# MCU_et_Communication.net
KiCad netlist of a schematic drawn in Altium Designer
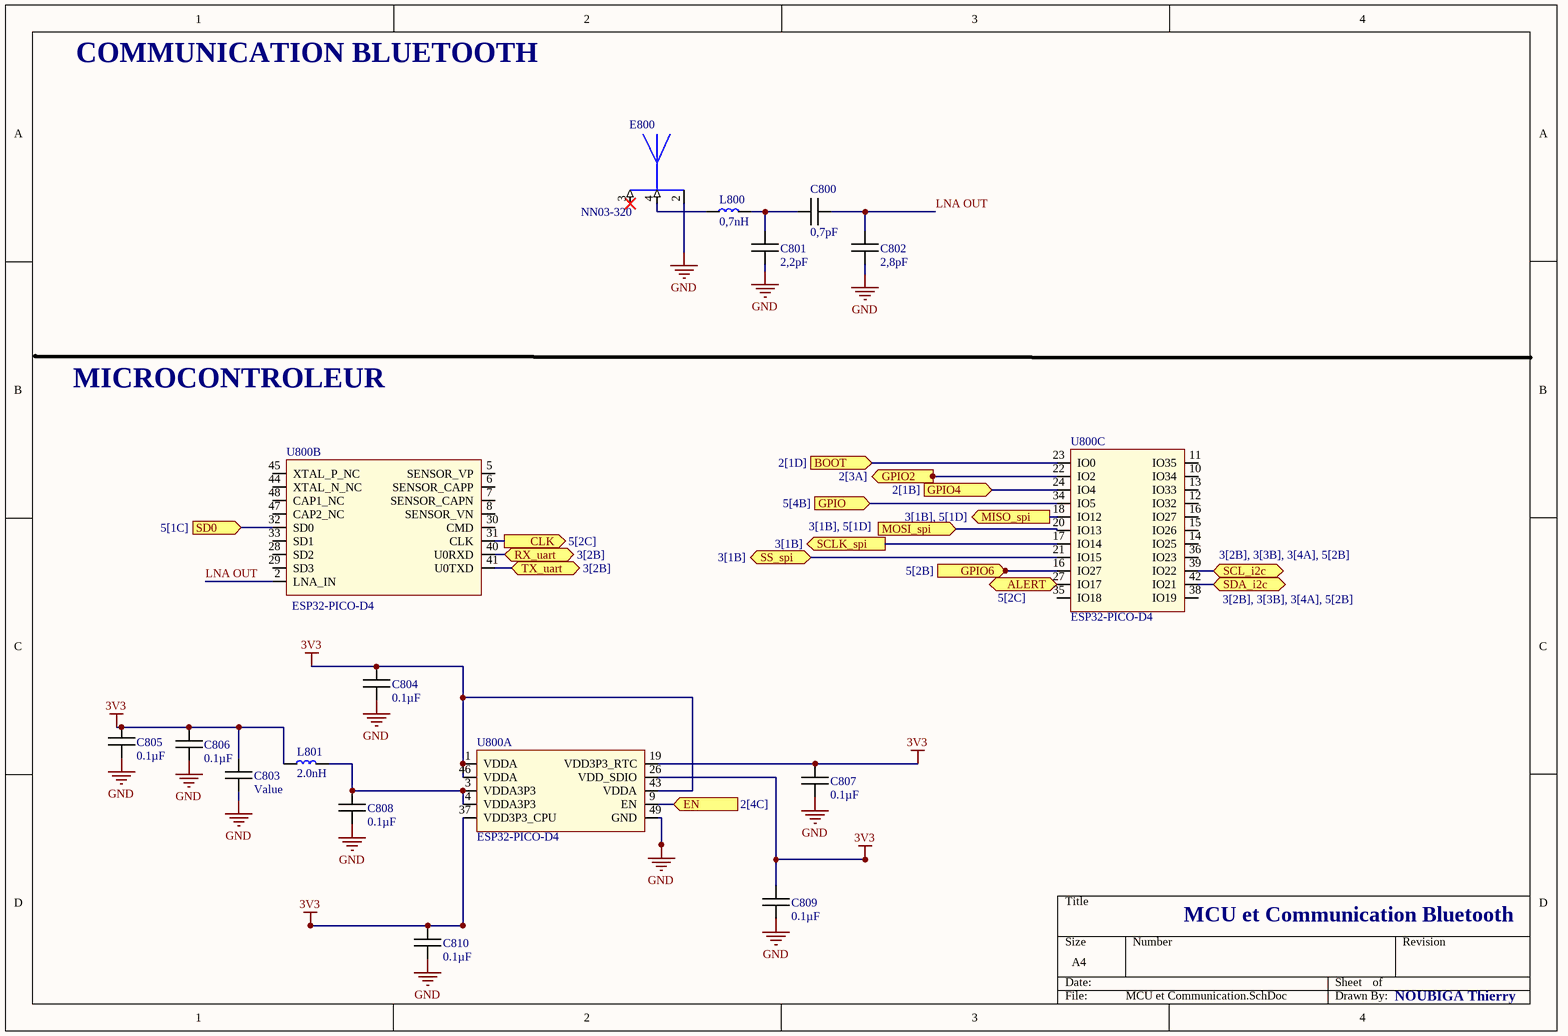
[diagram p0: MCU et Communication.SchDoc]

(export (version "E")
  (design (tool "Eeschema 10.0.6"))
  (components
    (comp (ref "C800")
      (value "0,7pF")
      (footprint "CAPC1005X06N")
      (libsource (lib "SCHLibrary") (part "Capacitor"))
    )
    (comp (ref "C801")
      (value "2,2pF")
      (footprint "CAPC1005X06N")
      (libsource (lib "SCHLibrary") (part "Capacitor"))
    )
    (comp (ref "C802")
      (value "2,8pF")
      (footprint "CAPC1005X06N")
      (libsource (lib "SCHLibrary") (part "Capacitor"))
    )
    (comp (ref "C803")
      (value "Value")
      (footprint "CAPC1005X06N")
      (libsource (lib "SCHLibrary") (part "Capacitor"))
    )
    (comp (ref "C804")
      (value "0.1µF")
      (footprint "CAPC1005X06N")
      (libsource (lib "SCHLibrary") (part "Capacitor"))
    )
    (comp (ref "C805")
      (value "0.1µF")
      (footprint "CAPC1005X06N")
      (libsource (lib "SCHLibrary") (part "Capacitor"))
    )
    (comp (ref "C806")
      (value "0.1µF")
      (footprint "CAPC1005X06N")
      (libsource (lib "SCHLibrary") (part "Capacitor"))
    )
    (comp (ref "C807")
      (value "0.1µF")
      (footprint "CAPC1005X06N")
      (libsource (lib "SCHLibrary") (part "Capacitor"))
    )
    (comp (ref "C808")
      (value "0.1µF")
      (footprint "CAPC1005X06N")
      (libsource (lib "SCHLibrary") (part "Capacitor"))
    )
    (comp (ref "C809")
      (value "0.1µF")
      (footprint "CAPC1005X06N")
      (libsource (lib "SCHLibrary") (part "Capacitor"))
    )
    (comp (ref "C810")
      (value "0.1µF")
      (footprint "CAPC1005X06N")
      (libsource (lib "SCHLibrary") (part "Capacitor"))
    )
    (comp (ref "E800")
      (value "NN03-320")
      (footprint "XCVR_NN03-320")
      (fields (field (name "MOUSER PART NUMBER") "128-NN03-320"))
      (libsource (lib "SCHLibrary") (part "NN03-320"))
    )
    (comp (ref "L800")
      (value "0,7nH")
      (footprint "LQPC1005X06N")
      (libsource (lib "SCHLibrary") (part "Bobine"))
    )
    (comp (ref "L801")
      (value "2.0nH")
      (footprint "LQPC1005X06N")
      (libsource (lib "SCHLibrary") (part "Bobine"))
    )
    (comp (ref "U800")
      (value "ESP32-PICO-D4")
      (footprint "PQFN50P700X700X104_HS-49N")
      (libsource (lib "") (part "ESP32_2"))
    )
  )
  (nets
    (net (code "1") (name "/ALERT") (class "Default")
      (node (ref "U800") (pin "27") (pinfunction "IO17_27") (pintype "passive"))
    )
    (net (code "2") (name "/BOOT") (class "Default")
      (node (ref "U800") (pin "23") (pinfunction "IO0_23") (pintype "passive"))
    )
    (net (code "3") (name "/CLK") (class "Default")
      (node (ref "U800") (pin "31") (pinfunction "CLK_31") (pintype "passive"))
    )
    (net (code "4") (name "/EN") (class "Default")
      (node (ref "U800") (pin "9") (pinfunction "EN_9") (pintype "passive"))
    )
    (net (code "5") (name "/GPIO") (class "Default")
      (node (ref "U800") (pin "34") (pinfunction "IO5_34") (pintype "passive"))
    )
    (net (code "6") (name "/GPIO2") (class "Default")
      (node (ref "U800") (pin "22") (pinfunction "IO2_22") (pintype "passive"))
    )
    (net (code "7") (name "/GPIO4") (class "Default")
      (node (ref "U800") (pin "24") (pinfunction "IO4_24") (pintype "passive"))
    )
    (net (code "8") (name "/GPIO6") (class "Default")
      (node (ref "U800") (pin "16") (pinfunction "IO27_16") (pintype "passive"))
    )
    (net (code "9") (name "/LNA OUT") (class "Default")
      (node (ref "C800") (pin "2") (pinfunction "2_2") (pintype "passive"))
      (node (ref "C802") (pin "1") (pinfunction "1_1") (pintype "passive"))
      (node (ref "U800") (pin "2") (pinfunction "LNA_IN_2") (pintype "passive"))
    )
    (net (code "10") (name "/MISO_spi") (class "Default")
      (node (ref "U800") (pin "18") (pinfunction "IO12_18") (pintype "passive"))
    )
    (net (code "11") (name "/MOSI_spi") (class "Default")
      (node (ref "U800") (pin "20") (pinfunction "IO13_20") (pintype "passive"))
    )
    (net (code "12") (name "/RX_uart") (class "Default")
      (node (ref "U800") (pin "40") (pinfunction "U0RXD_40") (pintype "passive"))
    )
    (net (code "13") (name "/SCLK_spi") (class "Default")
      (node (ref "U800") (pin "17") (pinfunction "IO14_17") (pintype "passive"))
    )
    (net (code "14") (name "/SCL_i2c") (class "Default")
      (node (ref "U800") (pin "39") (pinfunction "IO22_39") (pintype "passive"))
    )
    (net (code "15") (name "/SD0") (class "Default")
      (node (ref "U800") (pin "32") (pinfunction "SD0_32") (pintype "passive"))
    )
    (net (code "16") (name "/SDA_i2c") (class "Default")
      (node (ref "U800") (pin "42") (pinfunction "IO21_42") (pintype "passive"))
    )
    (net (code "17") (name "/SS_spi") (class "Default")
      (node (ref "U800") (pin "21") (pinfunction "IO15_21") (pintype "passive"))
    )
    (net (code "18") (name "/TX_uart") (class "Default")
      (node (ref "U800") (pin "41") (pinfunction "U0TXD_41") (pintype "passive"))
    )
    (net (code "19") (name "3V3") (class "Default")
      (node (ref "C803") (pin "1") (pinfunction "1_1") (pintype "passive"))
      (node (ref "C804") (pin "2") (pinfunction "2_2") (pintype "passive"))
      (node (ref "C805") (pin "2") (pinfunction "2_2") (pintype "passive"))
      (node (ref "C806") (pin "2") (pinfunction "2_2") (pintype "passive"))
      (node (ref "C807") (pin "1") (pinfunction "1_1") (pintype "passive"))
      (node (ref "C809") (pin "2") (pinfunction "2_2") (pintype "passive"))
      (node (ref "C810") (pin "1") (pinfunction "1_1") (pintype "passive"))
      (node (ref "L801") (pin "1") (pinfunction "1_1") (pintype "passive"))
      (node (ref "U800") (pin "1") (pinfunction "VDDA_1") (pintype "passive"))
      (node (ref "U800") (pin "19") (pinfunction "VDD3P3_RTC_19") (pintype "passive"))
      (node (ref "U800") (pin "26") (pinfunction "VDD_SDIO_26") (pintype "passive"))
      (node (ref "U800") (pin "37") (pinfunction "VDD3P3_CPU_37") (pintype "passive"))
      (node (ref "U800") (pin "43") (pinfunction "VDDA_43") (pintype "passive"))
      (node (ref "U800") (pin "46") (pinfunction "VDDA_46") (pintype "passive"))
    )
    (net (code "20") (name "GND") (class "Default")
      (node (ref "C801") (pin "2") (pinfunction "2_2") (pintype "passive"))
      (node (ref "C802") (pin "2") (pinfunction "2_2") (pintype "passive"))
      (node (ref "C803") (pin "2") (pinfunction "2_2") (pintype "passive"))
      (node (ref "C804") (pin "1") (pinfunction "1_1") (pintype "passive"))
      (node (ref "C805") (pin "1") (pinfunction "1_1") (pintype "passive"))
      (node (ref "C806") (pin "1") (pinfunction "1_1") (pintype "passive"))
      (node (ref "C807") (pin "2") (pinfunction "2_2") (pintype "passive"))
      (node (ref "C808") (pin "1") (pinfunction "1_1") (pintype "passive"))
      (node (ref "C809") (pin "1") (pinfunction "1_1") (pintype "passive"))
      (node (ref "C810") (pin "2") (pinfunction "2_2") (pintype "passive"))
      (node (ref "E800") (pin "2") (pinfunction "GROUND_2") (pintype "power_in"))
      (node (ref "U800") (pin "49") (pinfunction "GND_49") (pintype "passive"))
    )
    (net (code "21") (name "Net-(C800-Pad1)") (class "Default")
      (node (ref "C800") (pin "1") (pinfunction "1_1") (pintype "passive"))
      (node (ref "C801") (pin "1") (pinfunction "1_1") (pintype "passive"))
      (node (ref "L800") (pin "2") (pinfunction "2_2") (pintype "passive"))
    )
    (net (code "22") (name "Net-(C808-Pad2)") (class "Default")
      (node (ref "C808") (pin "2") (pinfunction "2_2") (pintype "passive"))
      (node (ref "L801") (pin "2") (pinfunction "2_2") (pintype "passive"))
      (node (ref "U800") (pin "3") (pinfunction "VDDA3P3_3") (pintype "passive"))
      (node (ref "U800") (pin "4") (pinfunction "VDDA3P3_4") (pintype "passive"))
    )
    (net (code "23") (name "Net-(E800-FEED_GNSS)") (class "Default")
      (node (ref "E800") (pin "4") (pinfunction "FEED_GNSS_4") (pintype "input"))
      (node (ref "L800") (pin "1") (pinfunction "1_1") (pintype "passive"))
    )
    (net (code "24") (name "unconnected-(E800-FEED_BLUETOOTH-Pad3)") (class "Default")
      (node (ref "E800") (pin "3") (pinfunction "FEED_BLUETOOTH_3") (pintype "input+no_connect"))
    )
    (net (code "25") (name "unconnected-(U800B-CAP1_NC-Pad48)") (class "Default")
      (node (ref "U800") (pin "48") (pinfunction "CAP1_NC_48") (pintype "passive"))
    )
    (net (code "26") (name "unconnected-(U800B-CAP2_NC-Pad47)") (class "Default")
      (node (ref "U800") (pin "47") (pinfunction "CAP2_NC_47") (pintype "passive"))
    )
    (net (code "27") (name "unconnected-(U800B-CMD-Pad30)") (class "Default")
      (node (ref "U800") (pin "30") (pinfunction "CMD_30") (pintype "passive"))
    )
    (net (code "28") (name "unconnected-(U800B-SD1-Pad33)") (class "Default")
      (node (ref "U800") (pin "33") (pinfunction "SD1_33") (pintype "passive"))
    )
    (net (code "29") (name "unconnected-(U800B-SD2-Pad28)") (class "Default")
      (node (ref "U800") (pin "28") (pinfunction "SD2_28") (pintype "passive"))
    )
    (net (code "30") (name "unconnected-(U800B-SD3-Pad29)") (class "Default")
      (node (ref "U800") (pin "29") (pinfunction "SD3_29") (pintype "passive"))
    )
    (net (code "31") (name "unconnected-(U800B-SENSOR_CAPN-Pad7)") (class "Default")
      (node (ref "U800") (pin "7") (pinfunction "SENSOR_CAPN_7") (pintype "passive"))
    )
    (net (code "32") (name "unconnected-(U800B-SENSOR_CAPP-Pad6)") (class "Default")
      (node (ref "U800") (pin "6") (pinfunction "SENSOR_CAPP_6") (pintype "passive"))
    )
    (net (code "33") (name "unconnected-(U800B-SENSOR_VN-Pad8)") (class "Default")
      (node (ref "U800") (pin "8") (pinfunction "SENSOR_VN_8") (pintype "passive"))
    )
    (net (code "34") (name "unconnected-(U800B-SENSOR_VP-Pad5)") (class "Default")
      (node (ref "U800") (pin "5") (pinfunction "SENSOR_VP_5") (pintype "passive"))
    )
    (net (code "35") (name "unconnected-(U800B-XTAL_N_NC-Pad44)") (class "Default")
      (node (ref "U800") (pin "44") (pinfunction "XTAL_N_NC_44") (pintype "passive"))
    )
    (net (code "36") (name "unconnected-(U800B-XTAL_P_NC-Pad45)") (class "Default")
      (node (ref "U800") (pin "45") (pinfunction "XTAL_P_NC_45") (pintype "passive"))
    )
    (net (code "37") (name "unconnected-(U800C-IO18-Pad35)") (class "Default")
      (node (ref "U800") (pin "35") (pinfunction "IO18_35") (pintype "passive"))
    )
    (net (code "38") (name "unconnected-(U800C-IO19-Pad38)") (class "Default")
      (node (ref "U800") (pin "38") (pinfunction "IO19_38") (pintype "passive"))
    )
    (net (code "39") (name "unconnected-(U800C-IO23-Pad36)") (class "Default")
      (node (ref "U800") (pin "36") (pinfunction "IO23_36") (pintype "passive"))
    )
    (net (code "40") (name "unconnected-(U800C-IO25-Pad14)") (class "Default")
      (node (ref "U800") (pin "14") (pinfunction "IO25_14") (pintype "passive"))
    )
    (net (code "41") (name "unconnected-(U800C-IO26-Pad15)") (class "Default")
      (node (ref "U800") (pin "15") (pinfunction "IO26_15") (pintype "passive"))
    )
    (net (code "42") (name "unconnected-(U800C-IO27-Pad16)") (class "Default")
      (node (ref "U800") (pin "16") (pinfunction "IO27_16") (pintype "passive"))
    )
    (net (code "43") (name "unconnected-(U800C-IO32-Pad12)") (class "Default")
      (node (ref "U800") (pin "12") (pinfunction "IO32_12") (pintype "passive"))
    )
    (net (code "44") (name "unconnected-(U800C-IO33-Pad13)") (class "Default")
      (node (ref "U800") (pin "13") (pinfunction "IO33_13") (pintype "passive"))
    )
    (net (code "45") (name "unconnected-(U800C-IO34-Pad10)") (class "Default")
      (node (ref "U800") (pin "10") (pinfunction "IO34_10") (pintype "passive"))
    )
    (net (code "46") (name "unconnected-(U800C-IO35-Pad11)") (class "Default")
      (node (ref "U800") (pin "11") (pinfunction "IO35_11") (pintype "passive"))
    )
  )
)
